# G021H.net
KiCad netlist of a schematic drawn in EAGLE
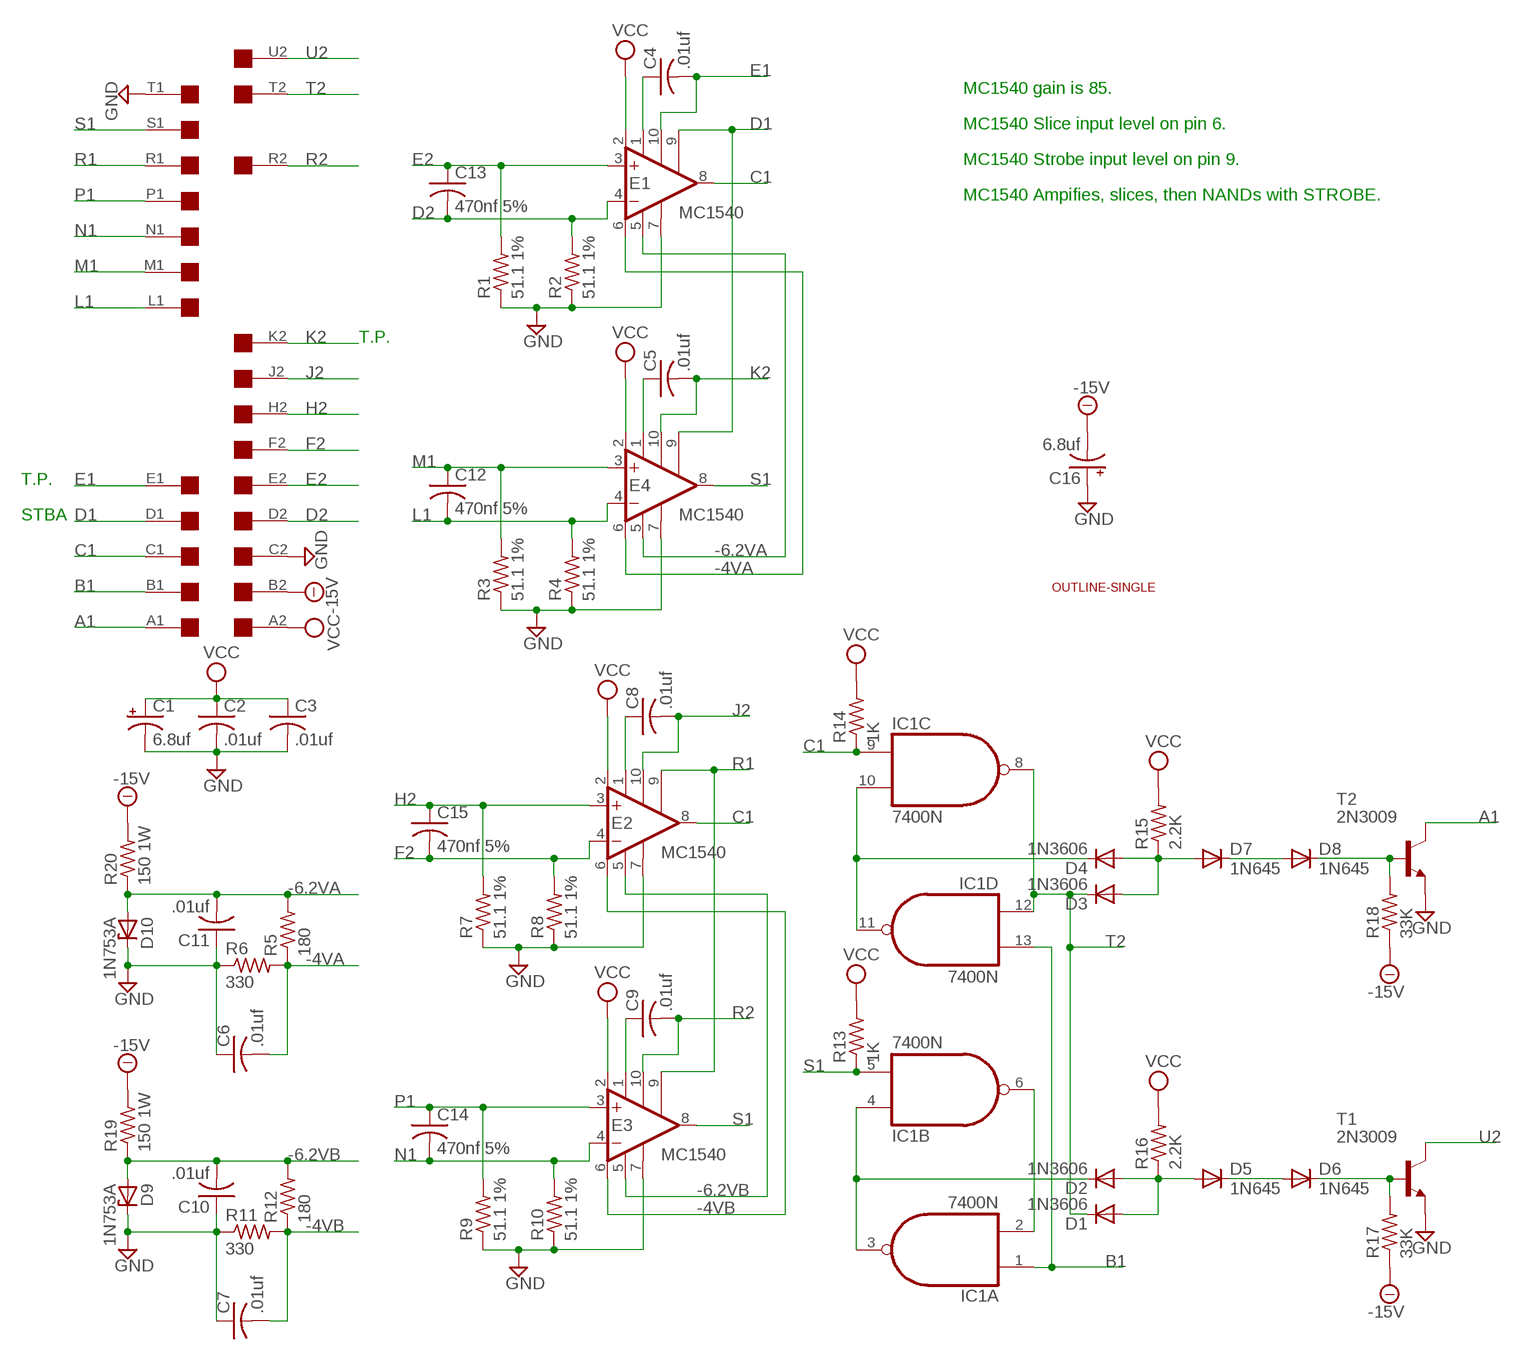
[diagram p0: schematic, sheet 1]

(export (version "E")
  (design (tool "Eeschema 10.0.6"))
  (components
    (comp (ref "C1")
      (value "6.8uf")
      (footprint "eagle-import:E22-6")
      (libsource (lib "eagle-import") (part "CPOL-USE22-6AXIAL"))
    )
    (comp (ref "C2")
      (value ".01uf")
      (footprint "eagle-import:C050-025X075")
      (libsource (lib "eagle-import") (part "C-US050-025X075"))
    )
    (comp (ref "C3")
      (value ".01uf")
      (footprint "eagle-import:C050-025X075")
      (libsource (lib "eagle-import") (part "C-US050-025X075"))
    )
    (comp (ref "C4")
      (value ".01uf")
      (footprint "eagle-import:C050-025X075")
      (libsource (lib "eagle-import") (part "C-US050-025X075"))
    )
    (comp (ref "C5")
      (value ".01uf")
      (footprint "eagle-import:C050-025X075")
      (libsource (lib "eagle-import") (part "C-US050-025X075"))
    )
    (comp (ref "C6")
      (value ".01uf")
      (footprint "eagle-import:C050-025X075")
      (libsource (lib "eagle-import") (part "C-US050-025X075"))
    )
    (comp (ref "C7")
      (value ".01uf")
      (footprint "eagle-import:C050-025X075")
      (libsource (lib "eagle-import") (part "C-US050-025X075"))
    )
    (comp (ref "C8")
      (value ".01uf")
      (footprint "eagle-import:C050-025X075")
      (libsource (lib "eagle-import") (part "C-US050-025X075"))
    )
    (comp (ref "C9")
      (value ".01uf")
      (footprint "eagle-import:C050-025X075")
      (libsource (lib "eagle-import") (part "C-US050-025X075"))
    )
    (comp (ref "C10")
      (value ".01uf")
      (footprint "eagle-import:C050-025X075")
      (libsource (lib "eagle-import") (part "C-US050-025X075"))
    )
    (comp (ref "C11")
      (value ".01uf")
      (footprint "eagle-import:C050-025X075")
      (libsource (lib "eagle-import") (part "C-US050-025X075"))
    )
    (comp (ref "C12")
      (value "470nf 5%")
      (footprint "eagle-import:C050-025X075")
      (libsource (lib "eagle-import") (part "C-US050-025X075"))
    )
    (comp (ref "C13")
      (value "470nf 5%")
      (footprint "eagle-import:C050-025X075")
      (libsource (lib "eagle-import") (part "C-US050-025X075"))
    )
    (comp (ref "C14")
      (value "470nf 5%")
      (footprint "eagle-import:C050-025X075")
      (libsource (lib "eagle-import") (part "C-US050-025X075"))
    )
    (comp (ref "C15")
      (value "470nf 5%")
      (footprint "eagle-import:C050-025X075")
      (libsource (lib "eagle-import") (part "C-US050-025X075"))
    )
    (comp (ref "C16")
      (value "6.8uf")
      (footprint "eagle-import:E22-6")
      (libsource (lib "eagle-import") (part "CPOL-USE22-6AXIAL"))
    )
    (comp (ref "D1")
      (value "1N3606")
      (footprint "eagle-import:DO35-10")
      (libsource (lib "eagle-import") (part "1N4148"))
    )
    (comp (ref "D2")
      (value "1N3606")
      (footprint "eagle-import:DO35-10")
      (libsource (lib "eagle-import") (part "1N4148"))
    )
    (comp (ref "D3")
      (value "1N3606")
      (footprint "eagle-import:DO35-10")
      (libsource (lib "eagle-import") (part "1N4148"))
    )
    (comp (ref "D4")
      (value "1N3606")
      (footprint "eagle-import:DO35-10")
      (libsource (lib "eagle-import") (part "1N4148"))
    )
    (comp (ref "D5")
      (value "1N645")
      (footprint "eagle-import:DO35-10")
      (libsource (lib "eagle-import") (part "1N4148"))
    )
    (comp (ref "D6")
      (value "1N645")
      (footprint "eagle-import:DO35-10")
      (libsource (lib "eagle-import") (part "1N4148"))
    )
    (comp (ref "D7")
      (value "1N645")
      (footprint "eagle-import:DO35-10")
      (libsource (lib "eagle-import") (part "1N4148"))
    )
    (comp (ref "D8")
      (value "1N645")
      (footprint "eagle-import:DO35-10")
      (libsource (lib "eagle-import") (part "1N4148"))
    )
    (comp (ref "D9")
      (value "1N753A")
      (footprint "eagle-import:F126Z10")
      (libsource (lib "eagle-import") (part "ZENER-DIODEF126-10"))
    )
    (comp (ref "D10")
      (value "1N753A")
      (footprint "eagle-import:F126Z10")
      (libsource (lib "eagle-import") (part "ZENER-DIODEF126-10"))
    )
    (comp (ref "E1")
      (value "MC1540")
      (footprint "eagle-import:602B")
      (libsource (lib "eagle-import") (part "MC1540G"))
    )
    (comp (ref "E2")
      (value "MC1540")
      (footprint "eagle-import:602B")
      (libsource (lib "eagle-import") (part "MC1540G"))
    )
    (comp (ref "E3")
      (value "MC1540")
      (footprint "eagle-import:602B")
      (libsource (lib "eagle-import") (part "MC1540G"))
    )
    (comp (ref "E4")
      (value "MC1540")
      (footprint "eagle-import:602B")
      (libsource (lib "eagle-import") (part "MC1540G"))
    )
    (comp (ref "IC1")
      (value "7400N")
      (footprint "eagle-import:DIL14")
      (libsource (lib "eagle-import") (part "7400N"))
    )
    (comp (ref "R1")
      (value "51.1 1%")
      (footprint "eagle-import:0207_10")
      (libsource (lib "eagle-import") (part "R-US_0207/10"))
    )
    (comp (ref "R2")
      (value "51.1 1%")
      (footprint "eagle-import:0207_10")
      (libsource (lib "eagle-import") (part "R-US_0207/10"))
    )
    (comp (ref "R3")
      (value "51.1 1%")
      (footprint "eagle-import:0207_10")
      (libsource (lib "eagle-import") (part "R-US_0207/10"))
    )
    (comp (ref "R4")
      (value "51.1 1%")
      (footprint "eagle-import:0207_10")
      (libsource (lib "eagle-import") (part "R-US_0207/10"))
    )
    (comp (ref "R5")
      (value "180")
      (footprint "eagle-import:0207_10")
      (libsource (lib "eagle-import") (part "R-US_0207/10"))
    )
    (comp (ref "R6")
      (value "330")
      (footprint "eagle-import:0207_10")
      (libsource (lib "eagle-import") (part "R-US_0207/10"))
    )
    (comp (ref "R7")
      (value "51.1 1%")
      (footprint "eagle-import:0207_10")
      (libsource (lib "eagle-import") (part "R-US_0207/10"))
    )
    (comp (ref "R8")
      (value "51.1 1%")
      (footprint "eagle-import:0207_10")
      (libsource (lib "eagle-import") (part "R-US_0207/10"))
    )
    (comp (ref "R9")
      (value "51.1 1%")
      (footprint "eagle-import:0207_10")
      (libsource (lib "eagle-import") (part "R-US_0207/10"))
    )
    (comp (ref "R10")
      (value "51.1 1%")
      (footprint "eagle-import:0207_10")
      (libsource (lib "eagle-import") (part "R-US_0207/10"))
    )
    (comp (ref "R11")
      (value "330")
      (footprint "eagle-import:0207_10")
      (libsource (lib "eagle-import") (part "R-US_0207/10"))
    )
    (comp (ref "R12")
      (value "180")
      (footprint "eagle-import:0207_10")
      (libsource (lib "eagle-import") (part "R-US_0207/10"))
    )
    (comp (ref "R13")
      (value "1K")
      (footprint "eagle-import:0207_10")
      (libsource (lib "eagle-import") (part "R-US_0207/10"))
    )
    (comp (ref "R14")
      (value "1K")
      (footprint "eagle-import:0207_10")
      (libsource (lib "eagle-import") (part "R-US_0207/10"))
    )
    (comp (ref "R15")
      (value "2.2K")
      (footprint "eagle-import:0207_10")
      (libsource (lib "eagle-import") (part "R-US_0207/10"))
    )
    (comp (ref "R16")
      (value "2.2K")
      (footprint "eagle-import:0207_10")
      (libsource (lib "eagle-import") (part "R-US_0207/10"))
    )
    (comp (ref "R17")
      (value "33K")
      (footprint "eagle-import:0207_10")
      (libsource (lib "eagle-import") (part "R-US_0207/10"))
    )
    (comp (ref "R18")
      (value "33K")
      (footprint "eagle-import:0207_10")
      (libsource (lib "eagle-import") (part "R-US_0207/10"))
    )
    (comp (ref "R19")
      (value "150 1W")
      (footprint "eagle-import:0414_15")
      (libsource (lib "eagle-import") (part "R-US_0414/15"))
    )
    (comp (ref "R20")
      (value "150 1W")
      (footprint "eagle-import:0414_15")
      (libsource (lib "eagle-import") (part "R-US_0414/15"))
    )
    (comp (ref "T1")
      (value "2N3009")
      (footprint "eagle-import:TO92")
      (libsource (lib "eagle-import") (part "2N3565"))
    )
    (comp (ref "T2")
      (value "2N3009")
      (footprint "eagle-import:TO92")
      (libsource (lib "eagle-import") (part "2N3565"))
    )
    (comp (ref "U$1")
      (value "SINGLE")
      (footprint "eagle-import:EDGE-CON2")
      (libsource (lib "eagle-import") (part "SINGLE"))
    )
    (comp (ref "U$2")
      (value "OUTLINE-SINGLE")
      (footprint "eagle-import:SINGLE")
      (libsource (lib "eagle-import") (part "OUTLINE-SINGLE"))
    )
  )
  (nets
    (net (code "1") (name "-15V") (class "Default")
      (node (ref "C16") (pin "-") (pinfunction "-_-") (pintype "passive"))
      (node (ref "R17") (pin "1") (pinfunction "1_1") (pintype "passive"))
      (node (ref "R18") (pin "1") (pinfunction "1_1") (pintype "passive"))
      (node (ref "R19") (pin "2") (pinfunction "2_2") (pintype "passive"))
      (node (ref "R20") (pin "2") (pinfunction "2_2") (pintype "passive"))
      (node (ref "U$1") (pin "B2") (pinfunction "1_B2") (pintype "passive"))
    )
    (net (code "2") (name "/-4VA") (class "Default")
      (node (ref "C6") (pin "2") (pinfunction "2_2") (pintype "passive"))
      (node (ref "E1") (pin "6") (pinfunction "SLICE_6") (pintype "bidirectional"))
      (node (ref "E4") (pin "6") (pinfunction "SLICE_6") (pintype "bidirectional"))
      (node (ref "R5") (pin "1") (pinfunction "1_1") (pintype "passive"))
      (node (ref "R6") (pin "2") (pinfunction "2_2") (pintype "passive"))
    )
    (net (code "3") (name "/-4VB") (class "Default")
      (node (ref "C7") (pin "2") (pinfunction "2_2") (pintype "passive"))
      (node (ref "E2") (pin "6") (pinfunction "SLICE_6") (pintype "bidirectional"))
      (node (ref "E3") (pin "6") (pinfunction "SLICE_6") (pintype "bidirectional"))
      (node (ref "R11") (pin "2") (pinfunction "2_2") (pintype "passive"))
      (node (ref "R12") (pin "1") (pinfunction "1_1") (pintype "passive"))
    )
    (net (code "4") (name "/-6.2VA") (class "Default")
      (node (ref "C11") (pin "2") (pinfunction "2_2") (pintype "passive"))
      (node (ref "D10") (pin "A") (pinfunction "A_A") (pintype "passive"))
      (node (ref "E1") (pin "5") (pinfunction "V-_5") (pintype "power_in"))
      (node (ref "E4") (pin "5") (pinfunction "V-_5") (pintype "power_in"))
      (node (ref "R20") (pin "1") (pinfunction "1_1") (pintype "passive"))
      (node (ref "R5") (pin "2") (pinfunction "2_2") (pintype "passive"))
    )
    (net (code "5") (name "/-6.2VB") (class "Default")
      (node (ref "C10") (pin "2") (pinfunction "2_2") (pintype "passive"))
      (node (ref "D9") (pin "A") (pinfunction "A_A") (pintype "passive"))
      (node (ref "E2") (pin "5") (pinfunction "V-_5") (pintype "power_in"))
      (node (ref "E3") (pin "5") (pinfunction "V-_5") (pintype "power_in"))
      (node (ref "R12") (pin "2") (pinfunction "2_2") (pintype "passive"))
      (node (ref "R19") (pin "1") (pinfunction "1_1") (pintype "passive"))
    )
    (net (code "6") (name "/A1") (class "Default")
      (node (ref "T2") (pin "1") (pinfunction "C_1") (pintype "passive"))
      (node (ref "U$1") (pin "A1") (pinfunction "1_A1") (pintype "passive"))
    )
    (net (code "7") (name "/B1") (class "Default")
      (node (ref "IC1") (pin "1") (pinfunction "I0_1") (pintype "input"))
      (node (ref "IC1") (pin "13") (pinfunction "I1_13") (pintype "input"))
      (node (ref "U$1") (pin "B1") (pinfunction "1_B1") (pintype "passive"))
    )
    (net (code "8") (name "/C1") (class "Default")
      (node (ref "E1") (pin "8") (pinfunction "OUT_8") (pintype "open_collector"))
      (node (ref "E2") (pin "8") (pinfunction "OUT_8") (pintype "open_collector"))
      (node (ref "IC1") (pin "9") (pinfunction "I0_9") (pintype "input"))
      (node (ref "R14") (pin "1") (pinfunction "1_1") (pintype "passive"))
      (node (ref "U$1") (pin "C1") (pinfunction "1_C1") (pintype "passive"))
    )
    (net (code "9") (name "/D1") (class "Default")
      (node (ref "E1") (pin "9") (pinfunction "ISTROBE_9") (pintype "passive"))
      (node (ref "E4") (pin "9") (pinfunction "ISTROBE_9") (pintype "passive"))
      (node (ref "U$1") (pin "D1") (pinfunction "1_D1") (pintype "passive"))
    )
    (net (code "10") (name "/D2") (class "Default")
      (node (ref "C13") (pin "2") (pinfunction "2_2") (pintype "passive"))
      (node (ref "E1") (pin "4") (pinfunction "-IN_4") (pintype "input"))
      (node (ref "R2") (pin "2") (pinfunction "2_2") (pintype "passive"))
      (node (ref "U$1") (pin "D2") (pinfunction "1_D2") (pintype "passive"))
    )
    (net (code "11") (name "/E1") (class "Default")
      (node (ref "C4") (pin "2") (pinfunction "2_2") (pintype "passive"))
      (node (ref "E1") (pin "10") (pinfunction "CEXTB_10") (pintype "passive"))
      (node (ref "U$1") (pin "E1") (pinfunction "1_E1") (pintype "passive"))
    )
    (net (code "12") (name "/E2") (class "Default")
      (node (ref "C13") (pin "1") (pinfunction "1_1") (pintype "passive"))
      (node (ref "E1") (pin "3") (pinfunction "+IN_3") (pintype "input"))
      (node (ref "R1") (pin "2") (pinfunction "2_2") (pintype "passive"))
      (node (ref "U$1") (pin "E2") (pinfunction "1_E2") (pintype "passive"))
    )
    (net (code "13") (name "/F2") (class "Default")
      (node (ref "C15") (pin "2") (pinfunction "2_2") (pintype "passive"))
      (node (ref "E2") (pin "4") (pinfunction "-IN_4") (pintype "input"))
      (node (ref "R8") (pin "2") (pinfunction "2_2") (pintype "passive"))
      (node (ref "U$1") (pin "F2") (pinfunction "1_F2") (pintype "passive"))
    )
    (net (code "14") (name "/H2") (class "Default")
      (node (ref "C15") (pin "1") (pinfunction "1_1") (pintype "passive"))
      (node (ref "E2") (pin "3") (pinfunction "+IN_3") (pintype "input"))
      (node (ref "R7") (pin "2") (pinfunction "2_2") (pintype "passive"))
      (node (ref "U$1") (pin "H2") (pinfunction "1_H2") (pintype "passive"))
    )
    (net (code "15") (name "/J2") (class "Default")
      (node (ref "C8") (pin "2") (pinfunction "2_2") (pintype "passive"))
      (node (ref "E2") (pin "10") (pinfunction "CEXTB_10") (pintype "passive"))
      (node (ref "U$1") (pin "J2") (pinfunction "1_J2") (pintype "passive"))
    )
    (net (code "16") (name "/K2") (class "Default")
      (node (ref "C5") (pin "2") (pinfunction "2_2") (pintype "passive"))
      (node (ref "E4") (pin "10") (pinfunction "CEXTB_10") (pintype "passive"))
      (node (ref "U$1") (pin "K2") (pinfunction "1_K2") (pintype "passive"))
    )
    (net (code "17") (name "/L1") (class "Default")
      (node (ref "C12") (pin "2") (pinfunction "2_2") (pintype "passive"))
      (node (ref "E4") (pin "4") (pinfunction "-IN_4") (pintype "input"))
      (node (ref "R4") (pin "2") (pinfunction "2_2") (pintype "passive"))
      (node (ref "U$1") (pin "L1") (pinfunction "1_L1") (pintype "passive"))
    )
    (net (code "18") (name "/M1") (class "Default")
      (node (ref "C12") (pin "1") (pinfunction "1_1") (pintype "passive"))
      (node (ref "E4") (pin "3") (pinfunction "+IN_3") (pintype "input"))
      (node (ref "R3") (pin "2") (pinfunction "2_2") (pintype "passive"))
      (node (ref "U$1") (pin "M1") (pinfunction "1_M1") (pintype "passive"))
    )
    (net (code "19") (name "/N1") (class "Default")
      (node (ref "C14") (pin "2") (pinfunction "2_2") (pintype "passive"))
      (node (ref "E3") (pin "4") (pinfunction "-IN_4") (pintype "input"))
      (node (ref "R10") (pin "2") (pinfunction "2_2") (pintype "passive"))
      (node (ref "U$1") (pin "N1") (pinfunction "1_N1") (pintype "passive"))
    )
    (net (code "20") (name "/P1") (class "Default")
      (node (ref "C14") (pin "1") (pinfunction "1_1") (pintype "passive"))
      (node (ref "E3") (pin "3") (pinfunction "+IN_3") (pintype "input"))
      (node (ref "R9") (pin "2") (pinfunction "2_2") (pintype "passive"))
      (node (ref "U$1") (pin "P1") (pinfunction "1_P1") (pintype "passive"))
    )
    (net (code "21") (name "/R1") (class "Default")
      (node (ref "E2") (pin "9") (pinfunction "ISTROBE_9") (pintype "passive"))
      (node (ref "E3") (pin "9") (pinfunction "ISTROBE_9") (pintype "passive"))
      (node (ref "U$1") (pin "R1") (pinfunction "1_R1") (pintype "passive"))
    )
    (net (code "22") (name "/R2") (class "Default")
      (node (ref "C9") (pin "2") (pinfunction "2_2") (pintype "passive"))
      (node (ref "E3") (pin "10") (pinfunction "CEXTB_10") (pintype "passive"))
      (node (ref "U$1") (pin "R2") (pinfunction "1_R2") (pintype "passive"))
    )
    (net (code "23") (name "/S1") (class "Default")
      (node (ref "E3") (pin "8") (pinfunction "OUT_8") (pintype "open_collector"))
      (node (ref "E4") (pin "8") (pinfunction "OUT_8") (pintype "open_collector"))
      (node (ref "IC1") (pin "5") (pinfunction "I1_5") (pintype "input"))
      (node (ref "R13") (pin "1") (pinfunction "1_1") (pintype "passive"))
      (node (ref "U$1") (pin "S1") (pinfunction "1_S1") (pintype "passive"))
    )
    (net (code "24") (name "/T2") (class "Default")
      (node (ref "D1") (pin "C") (pinfunction "C_C") (pintype "passive"))
      (node (ref "D3") (pin "C") (pinfunction "C_C") (pintype "passive"))
      (node (ref "IC1") (pin "12") (pinfunction "I0_12") (pintype "input"))
      (node (ref "IC1") (pin "8") (pinfunction "O_8") (pintype "output"))
      (node (ref "U$1") (pin "T2") (pinfunction "1_T2") (pintype "passive"))
    )
    (net (code "25") (name "/U2") (class "Default")
      (node (ref "T1") (pin "1") (pinfunction "C_1") (pintype "passive"))
      (node (ref "U$1") (pin "U2") (pinfunction "1_U2") (pintype "passive"))
    )
    (net (code "26") (name "GND") (class "Default")
      (node (ref "C1") (pin "-") (pinfunction "-_-") (pintype "passive"))
      (node (ref "C10") (pin "1") (pinfunction "1_1") (pintype "passive"))
      (node (ref "C11") (pin "1") (pinfunction "1_1") (pintype "passive"))
      (node (ref "C16") (pin "+") (pinfunction "+_+") (pintype "passive"))
      (node (ref "C2") (pin "2") (pinfunction "2_2") (pintype "passive"))
      (node (ref "C3") (pin "2") (pinfunction "2_2") (pintype "passive"))
      (node (ref "C6") (pin "1") (pinfunction "1_1") (pintype "passive"))
      (node (ref "C7") (pin "1") (pinfunction "1_1") (pintype "passive"))
      (node (ref "D10") (pin "C") (pinfunction "C_C") (pintype "passive"))
      (node (ref "D9") (pin "C") (pinfunction "C_C") (pintype "passive"))
      (node (ref "E1") (pin "7") (pinfunction "GND_7") (pintype "power_in"))
      (node (ref "E2") (pin "7") (pinfunction "GND_7") (pintype "power_in"))
      (node (ref "E3") (pin "7") (pinfunction "GND_7") (pintype "power_in"))
      (node (ref "E4") (pin "7") (pinfunction "GND_7") (pintype "power_in"))
      (node (ref "R1") (pin "1") (pinfunction "1_1") (pintype "passive"))
      (node (ref "R10") (pin "1") (pinfunction "1_1") (pintype "passive"))
      (node (ref "R11") (pin "1") (pinfunction "1_1") (pintype "passive"))
      (node (ref "R2") (pin "1") (pinfunction "1_1") (pintype "passive"))
      (node (ref "R3") (pin "1") (pinfunction "1_1") (pintype "passive"))
      (node (ref "R4") (pin "1") (pinfunction "1_1") (pintype "passive"))
      (node (ref "R6") (pin "1") (pinfunction "1_1") (pintype "passive"))
      (node (ref "R7") (pin "1") (pinfunction "1_1") (pintype "passive"))
      (node (ref "R8") (pin "1") (pinfunction "1_1") (pintype "passive"))
      (node (ref "R9") (pin "1") (pinfunction "1_1") (pintype "passive"))
      (node (ref "T1") (pin "3") (pinfunction "E_3") (pintype "passive"))
      (node (ref "T2") (pin "3") (pinfunction "E_3") (pintype "passive"))
      (node (ref "U$1") (pin "C2") (pinfunction "1_C2") (pintype "passive"))
      (node (ref "U$1") (pin "T1") (pinfunction "1_T1") (pintype "passive"))
    )
    (net (code "27") (name "Net-(D1-PadA)") (class "Default")
      (node (ref "D1") (pin "A") (pinfunction "A_A") (pintype "passive"))
      (node (ref "D2") (pin "A") (pinfunction "A_A") (pintype "passive"))
      (node (ref "D5") (pin "A") (pinfunction "A_A") (pintype "passive"))
      (node (ref "R16") (pin "1") (pinfunction "1_1") (pintype "passive"))
    )
    (net (code "28") (name "Net-(D3-PadA)") (class "Default")
      (node (ref "D3") (pin "A") (pinfunction "A_A") (pintype "passive"))
      (node (ref "D4") (pin "A") (pinfunction "A_A") (pintype "passive"))
      (node (ref "D7") (pin "A") (pinfunction "A_A") (pintype "passive"))
      (node (ref "R15") (pin "1") (pinfunction "1_1") (pintype "passive"))
    )
    (net (code "29") (name "Net-(D5-PadC)") (class "Default")
      (node (ref "D5") (pin "C") (pinfunction "C_C") (pintype "passive"))
      (node (ref "D6") (pin "A") (pinfunction "A_A") (pintype "passive"))
    )
    (net (code "30") (name "Net-(D7-PadC)") (class "Default")
      (node (ref "D7") (pin "C") (pinfunction "C_C") (pintype "passive"))
      (node (ref "D8") (pin "A") (pinfunction "A_A") (pintype "passive"))
    )
    (net (code "31") (name "Net-(E1-CEXTA)") (class "Default")
      (node (ref "C4") (pin "1") (pinfunction "1_1") (pintype "passive"))
      (node (ref "E1") (pin "1") (pinfunction "CEXTA_1") (pintype "passive"))
    )
    (net (code "32") (name "Net-(E2-CEXTA)") (class "Default")
      (node (ref "C8") (pin "1") (pinfunction "1_1") (pintype "passive"))
      (node (ref "E2") (pin "1") (pinfunction "CEXTA_1") (pintype "passive"))
    )
    (net (code "33") (name "Net-(E3-CEXTA)") (class "Default")
      (node (ref "C9") (pin "1") (pinfunction "1_1") (pintype "passive"))
      (node (ref "E3") (pin "1") (pinfunction "CEXTA_1") (pintype "passive"))
    )
    (net (code "34") (name "Net-(E4-CEXTA)") (class "Default")
      (node (ref "C5") (pin "1") (pinfunction "1_1") (pintype "passive"))
      (node (ref "E4") (pin "1") (pinfunction "CEXTA_1") (pintype "passive"))
    )
    (net (code "35") (name "Net-(IC1A-I1)") (class "Default")
      (node (ref "IC1") (pin "2") (pinfunction "I1_2") (pintype "input"))
      (node (ref "IC1") (pin "6") (pinfunction "O_6") (pintype "output"))
    )
    (net (code "36") (name "Net-(IC1A-O)") (class "Default")
      (node (ref "D2") (pin "C") (pinfunction "C_C") (pintype "passive"))
      (node (ref "IC1") (pin "3") (pinfunction "O_3") (pintype "output"))
      (node (ref "IC1") (pin "4") (pinfunction "I0_4") (pintype "input"))
    )
    (net (code "37") (name "Net-(IC1C-I1)") (class "Default")
      (node (ref "D4") (pin "C") (pinfunction "C_C") (pintype "passive"))
      (node (ref "IC1") (pin "10") (pinfunction "I1_10") (pintype "input"))
      (node (ref "IC1") (pin "11") (pinfunction "O_11") (pintype "output"))
    )
    (net (code "38") (name "Net-(T1-B)") (class "Default")
      (node (ref "D6") (pin "C") (pinfunction "C_C") (pintype "passive"))
      (node (ref "R17") (pin "2") (pinfunction "2_2") (pintype "passive"))
      (node (ref "T1") (pin "2") (pinfunction "B_2") (pintype "passive"))
    )
    (net (code "39") (name "Net-(T2-B)") (class "Default")
      (node (ref "D8") (pin "C") (pinfunction "C_C") (pintype "passive"))
      (node (ref "R18") (pin "2") (pinfunction "2_2") (pintype "passive"))
      (node (ref "T2") (pin "2") (pinfunction "B_2") (pintype "passive"))
    )
    (net (code "40") (name "VCC") (class "Default")
      (node (ref "C1") (pin "+") (pinfunction "+_+") (pintype "passive"))
      (node (ref "C2") (pin "1") (pinfunction "1_1") (pintype "passive"))
      (node (ref "C3") (pin "1") (pinfunction "1_1") (pintype "passive"))
      (node (ref "E1") (pin "2") (pinfunction "V+_2") (pintype "power_in"))
      (node (ref "E2") (pin "2") (pinfunction "V+_2") (pintype "power_in"))
      (node (ref "E3") (pin "2") (pinfunction "V+_2") (pintype "power_in"))
      (node (ref "E4") (pin "2") (pinfunction "V+_2") (pintype "power_in"))
      (node (ref "R13") (pin "2") (pinfunction "2_2") (pintype "passive"))
      (node (ref "R14") (pin "2") (pinfunction "2_2") (pintype "passive"))
      (node (ref "R15") (pin "2") (pinfunction "2_2") (pintype "passive"))
      (node (ref "R16") (pin "2") (pinfunction "2_2") (pintype "passive"))
      (node (ref "U$1") (pin "A2") (pinfunction "1_A2") (pintype "passive"))
    )
  )
)
